# STM32-PROX_3.net
KiCad netlist of a schematic drawn in Altium Designer
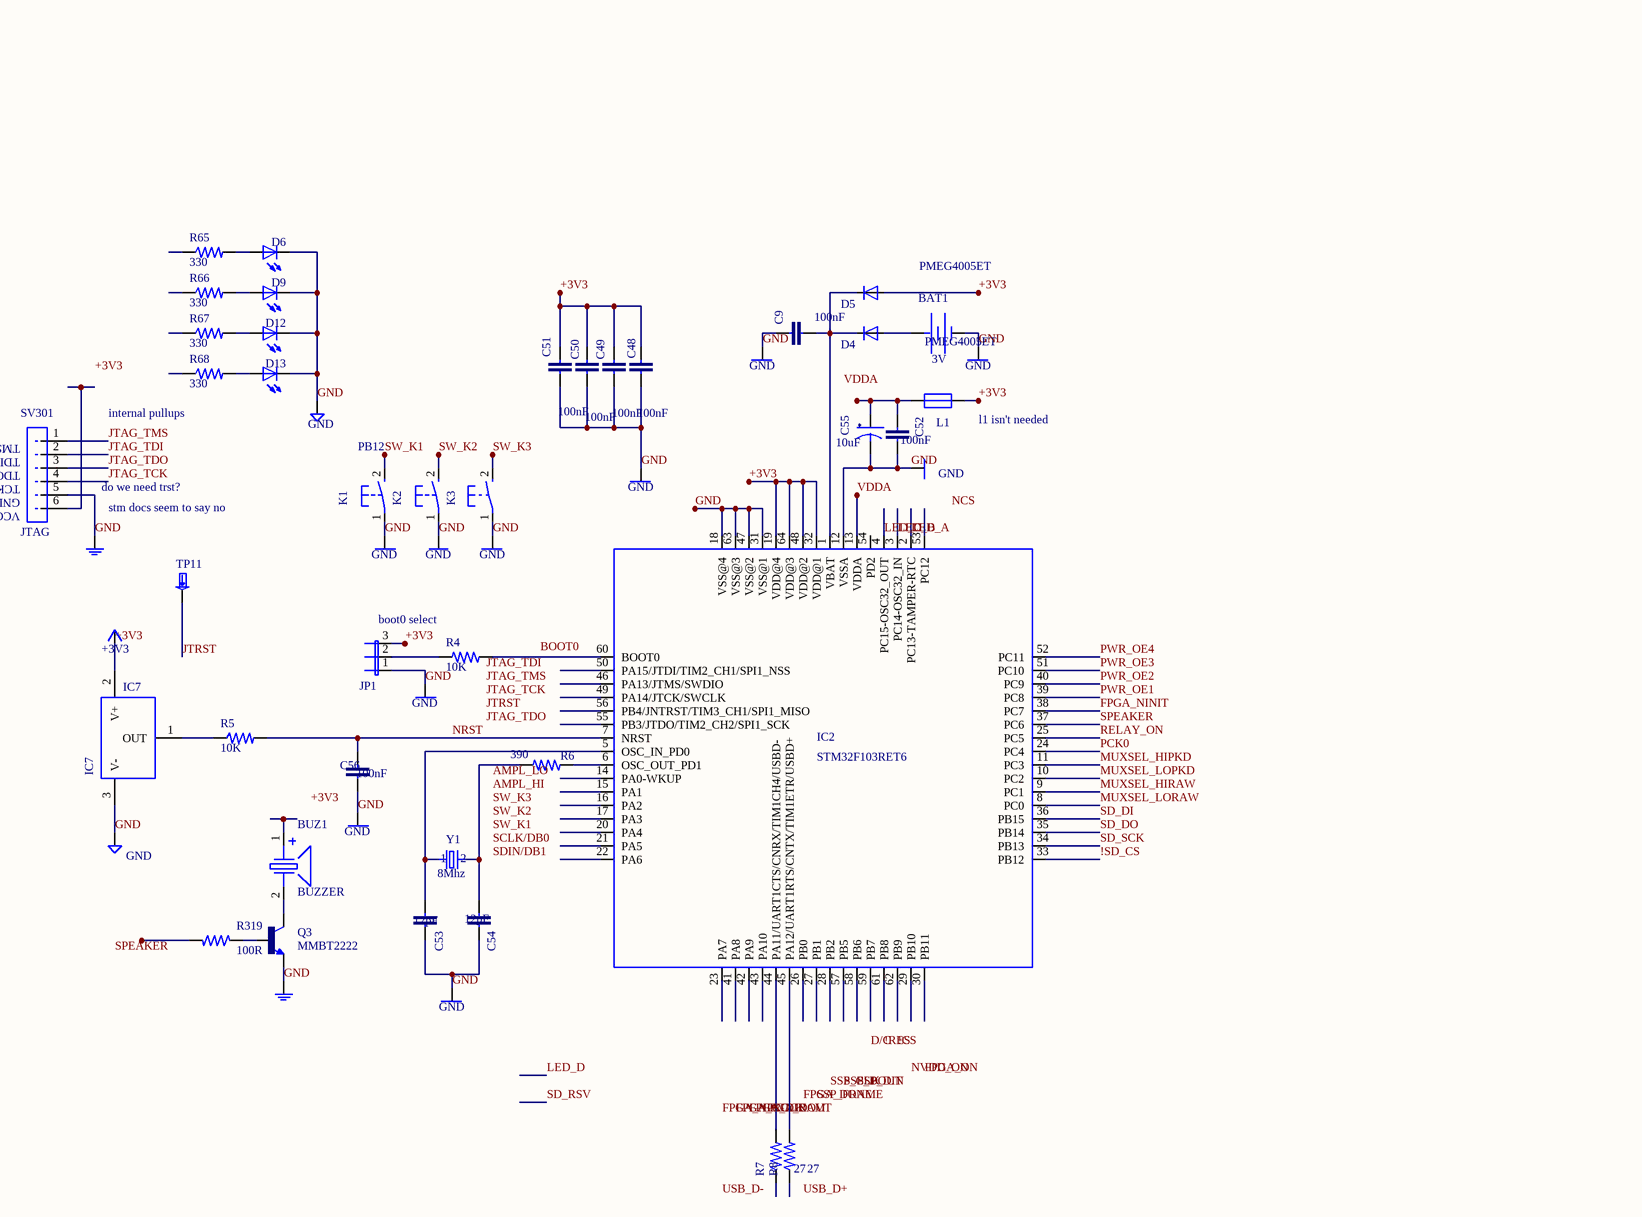
[diagram p0: STM32-PROX_3.SchDoc]

(export (version "E")
  (design (tool "Eeschema 10.0.6"))
  (components
    (comp (ref "BAT1")
      (value "3V")
      (footprint "NSL_SPARKFUN_BATTCON_12MM")
      (libsource (lib "Nullspace") (part "NSL_SPARKFUN_BATTERY12MM"))
    )
    (comp (ref "BUZ1") (value "BUZZER") (footprint "BUZZER") (libsource (lib "proxmark") (part "BUZZER")))
    (comp (ref "C9") (value "100nF") (footprint "0805") (libsource (lib "SparkFun") (part "CAP0805")))
    (comp (ref "C48") (value "100nF") (footprint "0805") (libsource (lib "SparkFun") (part "CAP0805")))
    (comp (ref "C49") (value "100nF") (footprint "0805") (libsource (lib "SparkFun") (part "CAP0805")))
    (comp (ref "C50") (value "100nF") (footprint "0805") (libsource (lib "SparkFun") (part "CAP0805")))
    (comp (ref "C51") (value "100nF") (footprint "0805") (libsource (lib "SparkFun") (part "CAP0805")))
    (comp (ref "C52") (value "100nF") (footprint "0805") (libsource (lib "SparkFun") (part "CAP0805")))
    (comp (ref "C53") (value "12pF") (footprint "0805") (libsource (lib "SparkFun") (part "CAP0805")))
    (comp (ref "C54") (value "12pF") (footprint "0805") (libsource (lib "SparkFun") (part "CAP0805")))
    (comp (ref "C55")
      (value "10uF")
      (footprint "EIA3216-KIT")
      (libsource (lib "SparkFun") (part "CAP_POL1206-KIT"))
    )
    (comp (ref "C56") (value "100nF") (footprint "0805") (libsource (lib "SparkFun") (part "CAP0805")))
    (comp (ref "D4")
      (value "PMEG4005ET")
      (footprint "SOT23-3")
      (libsource (lib "SparkFun") (part "DIODESOT23"))
    )
    (comp (ref "D5")
      (value "PMEG4005ET")
      (footprint "SOT23-3")
      (libsource (lib "SparkFun") (part "DIODESOT23"))
    )
    (comp (ref "D6") (value "~") (footprint "LED_0603") (libsource (lib "  merged") (part "LED")))
    (comp (ref "D9") (value "~") (footprint "LED_0603") (libsource (lib "  merged") (part "LED")))
    (comp (ref "D12") (value "~") (footprint "LED_0603") (libsource (lib "  merged") (part "LED")))
    (comp (ref "D13") (value "~") (footprint "LED_0603") (libsource (lib "  merged") (part "LED")))
    (comp (ref "GND1") (value "GND") (libsource (lib "") (part "GND_2")))
    (comp (ref "GND2") (value "GND") (libsource (lib "SparkFun") (part "GND")))
    (comp (ref "GND4") (value "GND") (libsource (lib "SparkFun") (part "GND")))
    (comp (ref "GND5") (value "GND") (libsource (lib "SparkFun") (part "GND")))
    (comp (ref "GND6") (value "GND") (libsource (lib "SparkFun") (part "GND")))
    (comp (ref "GND7") (value "GND") (libsource (lib "SparkFun") (part "GND")))
    (comp (ref "GND8") (value "GND") (libsource (lib "") (part "GND_2")))
    (comp (ref "GND43") (value "GND") (libsource (lib "") (part "GND_2")))
    (comp (ref "GND45") (value "GND") (libsource (lib "") (part "GND_1")))
    (comp (ref "GND46") (value "GND") (libsource (lib "SparkFun") (part "GND")))
    (comp (ref "IC2")
      (value "STM32F103RET6")
      (footprint "LQFP64_PACKAGE")
      (libsource (lib "Nullspace") (part "STM32F1_HIGH_DENSITY_LQFP64LQF64"))
    )
    (comp (ref "IC7") (value "~") (footprint "SOT23-3LEAD") (libsource (lib "  merged") (part "MCP100")))
    (comp (ref "JP1")
      (value "boot0 select")
      (footprint "JUMPER3")
      (libsource (lib "microbuilder") (part "JUMPER3"))
    )
    (comp (ref "K1") (value "~") (footprint "B3F-5XX") (libsource (lib "") (part "5-XX_1")))
    (comp (ref "K2") (value "~") (footprint "B3F-5XX") (libsource (lib "") (part "5-XX_1")))
    (comp (ref "K3") (value "~") (footprint "B3F-5XX") (libsource (lib "switch-omron") (part "5-XX")))
    (comp (ref "L1") (value "~") (footprint "0603") (libsource (lib "microbuilder") (part "FERRITE")))
    (comp (ref "Q3")
      (value "MMBT2222")
      (footprint "SOT-23-3")
      (libsource (lib "proxmark") (part "TRANSISTOR_NPNSOT23"))
    )
    (comp (ref "R4") (value "10K") (footprint "R0805") (libsource (lib "") (part "R-US_R0805_1")))
    (comp (ref "R5") (value "10K") (footprint "R0805") (libsource (lib "resistor") (part "R-US_R0805")))
    (comp (ref "R6") (value "390") (footprint "R0805") (libsource (lib "") (part "R-US_R0805_1")))
    (comp (ref "R7") (value "27") (footprint "R0805") (libsource (lib "resistor") (part "R-US_R0805")))
    (comp (ref "R8") (value "27") (footprint "R0805") (libsource (lib "resistor") (part "R-US_R0805")))
    (comp (ref "R65") (value "330") (footprint "RLC_0603") (libsource (lib "  merged") (part "RESISTOR0603")))
    (comp (ref "R66") (value "330") (footprint "RLC_0603") (libsource (lib "  merged") (part "RESISTOR0603")))
    (comp (ref "R67") (value "330") (footprint "RLC_0603") (libsource (lib "  merged") (part "RESISTOR0603")))
    (comp (ref "R68") (value "330") (footprint "RLC_0603") (libsource (lib "  merged") (part "RESISTOR0603")))
    (comp (ref "R319") (value "100R") (footprint "0603") (libsource (lib "proxmark") (part "R-US")))
    (comp (ref "SV301") (value "~") (footprint "HEADER-1X6") (libsource (lib "proxmark") (part "HEADER-1X6")))
    (comp (ref "TP11")
      (value "~")
      (footprint "KEYSTONE-PTH-TESTPOINT-5011")
      (libsource (lib "  merged") (part "TESTPADKEYSTONE-PTH"))
    )
    (comp (ref "U$10") (value "+3V3") (libsource (lib "supply1") (part "+3V3")))
    (comp (ref "V3") (value "~") (libsource (lib "proxmark") (part "AGND")))
    (comp (ref "V5") (value "~") (libsource (lib "") (part "AGND_1")))
    (comp (ref "V12") (value "GND") (libsource (lib "supply2") (part "GND")))
    (comp (ref "V40") (value "GND") (libsource (lib "supply2") (part "GND")))
    (comp (ref "Y1")
      (value "8Mhz")
      (footprint "CRYSTAL-TXC-7A")
      (libsource (lib "SparkFun-FreqCtrl") (part "CRYSTALTXC-7A"))
    )
  )
  (nets
    (net (code "3") (name "/!SD_CS") (class "Default")
      (node (ref "IC2") (pin "33") (pinfunction "PB12_33") (pintype "passive"))
    )
    (net (code "4") (name "/+3V3") (class "Default")
      (node (ref "C48") (pin "1") (pinfunction "1_1") (pintype "passive"))
      (node (ref "C49") (pin "1") (pinfunction "1_1") (pintype "passive"))
      (node (ref "C50") (pin "1") (pinfunction "1_1") (pintype "passive"))
      (node (ref "C51") (pin "1") (pinfunction "1_1") (pintype "passive"))
      (node (ref "D5") (pin "1") (pinfunction "A_1") (pintype "passive"))
      (node (ref "IC2") (pin "19") (pinfunction "VDD@4_19") (pintype "passive"))
      (node (ref "IC2") (pin "32") (pinfunction "VDD@1_32") (pintype "passive"))
      (node (ref "IC2") (pin "48") (pinfunction "VDD@2_48") (pintype "passive"))
      (node (ref "IC2") (pin "64") (pinfunction "VDD@3_64") (pintype "passive"))
      (node (ref "IC7") (pin "2") (pinfunction "V+_2") (pintype "passive"))
      (node (ref "JP1") (pin "3") (pinfunction "3_3") (pintype "passive"))
      (node (ref "L1") (pin "1") (pinfunction "P$1_1") (pintype "passive"))
      (node (ref "U$10") (pin "0") (pinfunction "+3V3_0") (pintype "passive"))
    )
    (net (code "13") (name "/FPGA_NINIT") (class "Default")
      (node (ref "IC2") (pin "38") (pinfunction "PC7_38") (pintype "passive"))
    )
    (net (code "16") (name "/GND") (class "Default")
      (node (ref "BAT1") (pin "GND") (pinfunction "-_GND") (pintype "passive"))
      (node (ref "C48") (pin "2") (pinfunction "2_2") (pintype "passive"))
      (node (ref "C49") (pin "2") (pinfunction "2_2") (pintype "passive"))
      (node (ref "C50") (pin "2") (pinfunction "2_2") (pintype "passive"))
      (node (ref "C51") (pin "2") (pinfunction "2_2") (pintype "passive"))
      (node (ref "C52") (pin "2") (pinfunction "2_2") (pintype "passive"))
      (node (ref "C53") (pin "1") (pinfunction "1_1") (pintype "passive"))
      (node (ref "C54") (pin "1") (pinfunction "1_1") (pintype "passive"))
      (node (ref "C55") (pin "C") (pinfunction "-_C") (pintype "passive"))
      (node (ref "C56") (pin "2") (pinfunction "2_2") (pintype "passive"))
      (node (ref "C9") (pin "1") (pinfunction "1_1") (pintype "passive"))
      (node (ref "D12") (pin "-") (pinfunction "C_-") (pintype "passive"))
      (node (ref "D13") (pin "-") (pinfunction "C_-") (pintype "passive"))
      (node (ref "D6") (pin "-") (pinfunction "C_-") (pintype "passive"))
      (node (ref "D9") (pin "-") (pinfunction "C_-") (pintype "passive"))
      (node (ref "GND1") (pin "0") (pinfunction "GND_0") (pintype "passive"))
      (node (ref "GND2") (pin "0") (pinfunction "GND_0") (pintype "passive"))
      (node (ref "GND4") (pin "0") (pinfunction "GND_0") (pintype "passive"))
      (node (ref "GND43") (pin "0") (pinfunction "GND_0") (pintype "passive"))
      (node (ref "GND45") (pin "0") (pinfunction "GND_0") (pintype "passive"))
      (node (ref "GND46") (pin "0") (pinfunction "GND_0") (pintype "passive"))
      (node (ref "GND5") (pin "0") (pinfunction "GND_0") (pintype "passive"))
      (node (ref "GND6") (pin "0") (pinfunction "GND_0") (pintype "passive"))
      (node (ref "GND7") (pin "0") (pinfunction "GND_0") (pintype "passive"))
      (node (ref "GND8") (pin "0") (pinfunction "GND_0") (pintype "passive"))
      (node (ref "IC2") (pin "12") (pinfunction "VSSA_12") (pintype "passive"))
      (node (ref "IC2") (pin "18") (pinfunction "VSS@4_18") (pintype "passive"))
      (node (ref "IC2") (pin "31") (pinfunction "VSS@1_31") (pintype "passive"))
      (node (ref "IC2") (pin "47") (pinfunction "VSS@2_47") (pintype "passive"))
      (node (ref "IC2") (pin "63") (pinfunction "VSS@3_63") (pintype "passive"))
      (node (ref "IC7") (pin "3") (pinfunction "V-_3") (pintype "passive"))
      (node (ref "JP1") (pin "1") (pinfunction "1_1") (pintype "passive"))
      (node (ref "K1") (pin "1") (pinfunction "P_1") (pintype "passive"))
      (node (ref "K2") (pin "1") (pinfunction "P_1") (pintype "passive"))
      (node (ref "K3") (pin "1") (pinfunction "P_1") (pintype "passive"))
      (node (ref "Q3") (pin "2") (pinfunction "E_2") (pintype "passive"))
      (node (ref "SV301") (pin "5") (pinfunction "5_5") (pintype "passive"))
      (node (ref "V12") (pin "0") (pinfunction "GND_0") (pintype "passive"))
      (node (ref "V3") (pin "0") (pinfunction "GND_0") (pintype "passive"))
      (node (ref "V40") (pin "0") (pinfunction "GND_0") (pintype "passive"))
      (node (ref "V5") (pin "0") (pinfunction "GND_0") (pintype "passive"))
    )
    (net (code "17") (name "/JTAG_TCK") (class "Default")
      (node (ref "SV301") (pin "4") (pinfunction "4_4") (pintype "passive"))
    )
    (net (code "18") (name "/JTAG_TDI") (class "Default")
      (node (ref "SV301") (pin "2") (pinfunction "2_2") (pintype "passive"))
    )
    (net (code "19") (name "/JTAG_TDO") (class "Default")
      (node (ref "SV301") (pin "3") (pinfunction "3_3") (pintype "passive"))
    )
    (net (code "20") (name "/JTAG_TMS") (class "Default")
      (node (ref "SV301") (pin "1") (pinfunction "1_1") (pintype "passive"))
    )
    (net (code "21") (name "/JTRST") (class "Default")
      (node (ref "TP11") (pin "A") (pinfunction "P$1_A") (pintype "passive"))
    )
    (net (code "22") (name "/LED_A") (class "Default")
      (node (ref "IC2") (pin "2") (pinfunction "PC13-TAMPER-RTC_2") (pintype "passive"))
    )
    (net (code "23") (name "/LED_B") (class "Default")
      (node (ref "IC2") (pin "3") (pinfunction "PC14-OSC32_IN_3") (pintype "passive"))
    )
    (net (code "24") (name "/LED_C") (class "Default")
      (node (ref "IC2") (pin "4") (pinfunction "PC15-OSC32_OUT_4") (pintype "passive"))
    )
    (net (code "26") (name "/MUXSEL_HIPKD") (class "Default")
      (node (ref "IC2") (pin "11") (pinfunction "PC3_11") (pintype "passive"))
    )
    (net (code "27") (name "/MUXSEL_HIRAW") (class "Default")
      (node (ref "IC2") (pin "9") (pinfunction "PC1_9") (pintype "passive"))
    )
    (net (code "28") (name "/MUXSEL_LOPKD") (class "Default")
      (node (ref "IC2") (pin "10") (pinfunction "PC2_10") (pintype "passive"))
    )
    (net (code "29") (name "/MUXSEL_LORAW") (class "Default")
      (node (ref "IC2") (pin "8") (pinfunction "PC0_8") (pintype "passive"))
    )
    (net (code "31") (name "/NRST") (class "Default")
      (node (ref "C56") (pin "1") (pinfunction "1_1") (pintype "passive"))
      (node (ref "IC2") (pin "7") (pinfunction "NRST_7") (pintype "passive"))
      (node (ref "R5") (pin "2") (pinfunction "2_2") (pintype "passive"))
    )
    (net (code "33") (name "/PCK0") (class "Default")
      (node (ref "IC2") (pin "24") (pinfunction "PC4_24") (pintype "passive"))
    )
    (net (code "34") (name "/PWR_OE1") (class "Default")
      (node (ref "IC2") (pin "39") (pinfunction "PC8_39") (pintype "passive"))
    )
    (net (code "35") (name "/PWR_OE2") (class "Default")
      (node (ref "IC2") (pin "40") (pinfunction "PC9_40") (pintype "passive"))
    )
    (net (code "36") (name "/PWR_OE3") (class "Default")
      (node (ref "IC2") (pin "51") (pinfunction "PC10_51") (pintype "passive"))
    )
    (net (code "37") (name "/PWR_OE4") (class "Default")
      (node (ref "IC2") (pin "52") (pinfunction "PC11_52") (pintype "passive"))
    )
    (net (code "38") (name "/RELAY_ON") (class "Default")
      (node (ref "IC2") (pin "25") (pinfunction "PC5_25") (pintype "passive"))
    )
    (net (code "41") (name "/SD_DI") (class "Default")
      (node (ref "IC2") (pin "36") (pinfunction "PB15_36") (pintype "passive"))
    )
    (net (code "42") (name "/SD_DO") (class "Default")
      (node (ref "IC2") (pin "35") (pinfunction "PB14_35") (pintype "passive"))
    )
    (net (code "44") (name "/SD_SCK") (class "Default")
      (node (ref "IC2") (pin "34") (pinfunction "PB13_34") (pintype "passive"))
    )
    (net (code "45") (name "/SPEAKER") (class "Default")
      (node (ref "IC2") (pin "37") (pinfunction "PC6_37") (pintype "passive"))
    )
    (net (code "50") (name "/SW_K1") (class "Default")
      (node (ref "K1") (pin "2") (pinfunction "S_2") (pintype "passive"))
    )
    (net (code "51") (name "/SW_K2") (class "Default")
      (node (ref "K2") (pin "2") (pinfunction "S_2") (pintype "passive"))
    )
    (net (code "52") (name "/SW_K3") (class "Default")
      (node (ref "K3") (pin "2") (pinfunction "S_2") (pintype "passive"))
    )
    (net (code "55") (name "/VDDA") (class "Default")
      (node (ref "IC2") (pin "13") (pinfunction "VDDA_13") (pintype "passive"))
    )
    (net (code "56") (name "Net-(BAT1-+)") (class "Default")
      (node (ref "BAT1") (pin "PWR@1") (pinfunction "+_PWR@1") (pintype "passive"))
      (node (ref "D4") (pin "1") (pinfunction "A_1") (pintype "passive"))
    )
    (net (code "57") (name "Net-(C55-+)") (class "Default")
      (node (ref "C52") (pin "1") (pinfunction "1_1") (pintype "passive"))
      (node (ref "C55") (pin "A") (pinfunction "+_A") (pintype "passive"))
      (node (ref "L1") (pin "2") (pinfunction "P$2_2") (pintype "passive"))
    )
    (net (code "58") (name "Net-(D4-C)") (class "Default")
      (node (ref "C9") (pin "2") (pinfunction "2_2") (pintype "passive"))
      (node (ref "D4") (pin "3") (pinfunction "C_3") (pintype "passive"))
      (node (ref "D5") (pin "3") (pinfunction "C_3") (pintype "passive"))
      (node (ref "IC2") (pin "1") (pinfunction "VBAT_1") (pintype "passive"))
    )
    (net (code "59") (name "Net-(D6-A)") (class "Default")
      (node (ref "D6") (pin "+") (pinfunction "A_+") (pintype "passive"))
      (node (ref "R65") (pin "2") (pinfunction "2_2") (pintype "passive"))
    )
    (net (code "60") (name "Net-(D9-A)") (class "Default")
      (node (ref "D9") (pin "+") (pinfunction "A_+") (pintype "passive"))
      (node (ref "R66") (pin "2") (pinfunction "2_2") (pintype "passive"))
    )
    (net (code "61") (name "Net-(D12-A)") (class "Default")
      (node (ref "D12") (pin "+") (pinfunction "A_+") (pintype "passive"))
      (node (ref "R67") (pin "2") (pinfunction "2_2") (pintype "passive"))
    )
    (net (code "62") (name "Net-(D13-A)") (class "Default")
      (node (ref "D13") (pin "+") (pinfunction "A_+") (pintype "passive"))
      (node (ref "R68") (pin "2") (pinfunction "2_2") (pintype "passive"))
    )
    (net (code "63") (name "Net-(IC2-BOOT0)") (class "Default")
      (node (ref "IC2") (pin "60") (pinfunction "BOOT0_60") (pintype "passive"))
      (node (ref "R4") (pin "2") (pinfunction "2_2") (pintype "passive"))
    )
    (net (code "64") (name "Net-(IC2-OSC_IN_PD0)") (class "Default")
      (node (ref "C53") (pin "2") (pinfunction "2_2") (pintype "passive"))
      (node (ref "IC2") (pin "5") (pinfunction "OSC_IN_PD0_5") (pintype "passive"))
      (node (ref "Y1") (pin "P$1") (pinfunction "1_P$1") (pintype "passive"))
    )
    (net (code "65") (name "Net-(IC2-OSC_OUT_PD1)") (class "Default")
      (node (ref "IC2") (pin "6") (pinfunction "OSC_OUT_PD1_6") (pintype "passive"))
      (node (ref "R6") (pin "2") (pinfunction "2_2") (pintype "passive"))
    )
    (net (code "66") (name "Net-(IC2-PA11{slash}UART1CTS{slash}CNRX{slash}TIM1CH4{slash}USBD-)") (class "Default")
      (node (ref "IC2") (pin "44") (pinfunction "PA11/UART1CTS/CNRX/TIM1CH4/USBD-_44") (pintype "passive"))
      (node (ref "R7") (pin "2") (pinfunction "2_2") (pintype "passive"))
    )
    (net (code "67") (name "Net-(IC2-PA12{slash}UART1RTS{slash}CNTX{slash}TIM1ETR{slash}USBD+)") (class "Default")
      (node (ref "IC2") (pin "45") (pinfunction "PA12/UART1RTS/CNTX/TIM1ETR/USBD+_45") (pintype "passive"))
      (node (ref "R8") (pin "2") (pinfunction "2_2") (pintype "passive"))
    )
    (net (code "68") (name "Net-(IC7-OUT)") (class "Default")
      (node (ref "IC7") (pin "1") (pinfunction "OUT_1") (pintype "passive"))
      (node (ref "R5") (pin "1") (pinfunction "1_1") (pintype "passive"))
    )
    (net (code "69") (name "Net-(JP1-Pad2)") (class "Default")
      (node (ref "JP1") (pin "2") (pinfunction "2_2") (pintype "passive"))
      (node (ref "R4") (pin "1") (pinfunction "1_1") (pintype "passive"))
    )
    (net (code "70") (name "Net-(Q3-B)") (class "Default")
      (node (ref "Q3") (pin "1") (pinfunction "B_1") (pintype "passive"))
      (node (ref "R319") (pin "1") (pinfunction "1_1") (pintype "passive"))
    )
    (net (code "71") (name "Net-(Q3-C)") (class "Default")
      (node (ref "BUZ1") (pin "2") (pinfunction "2_2") (pintype "passive"))
      (node (ref "Q3") (pin "3") (pinfunction "C_3") (pintype "passive"))
    )
    (net (code "72") (name "Net-(Y1-2)") (class "Default")
      (node (ref "C54") (pin "2") (pinfunction "2_2") (pintype "passive"))
      (node (ref "R6") (pin "1") (pinfunction "1_1") (pintype "passive"))
      (node (ref "Y1") (pin "P$2") (pinfunction "2_P$2") (pintype "passive"))
    )
    (net (code "73") (name "unconnected-(BUZ1-Pad1)") (class "Default")
      (node (ref "BUZ1") (pin "1") (pinfunction "1_1") (pintype "passive"))
    )
    (net (code "74") (name "unconnected-(IC2-PA0-WKUP-Pad14)") (class "Default")
      (node (ref "IC2") (pin "14") (pinfunction "PA0-WKUP_14") (pintype "passive"))
    )
    (net (code "75") (name "unconnected-(IC2-PA1-Pad15)") (class "Default")
      (node (ref "IC2") (pin "15") (pinfunction "PA1_15") (pintype "passive"))
    )
    (net (code "76") (name "unconnected-(IC2-PA2-Pad16)") (class "Default")
      (node (ref "IC2") (pin "16") (pinfunction "PA2_16") (pintype "passive"))
    )
    (net (code "77") (name "unconnected-(IC2-PA3-Pad17)") (class "Default")
      (node (ref "IC2") (pin "17") (pinfunction "PA3_17") (pintype "passive"))
    )
    (net (code "78") (name "unconnected-(IC2-PA4-Pad20)") (class "Default")
      (node (ref "IC2") (pin "20") (pinfunction "PA4_20") (pintype "passive"))
    )
    (net (code "79") (name "unconnected-(IC2-PA5-Pad21)") (class "Default")
      (node (ref "IC2") (pin "21") (pinfunction "PA5_21") (pintype "passive"))
    )
    (net (code "80") (name "unconnected-(IC2-PA6-Pad22)") (class "Default")
      (node (ref "IC2") (pin "22") (pinfunction "PA6_22") (pintype "passive"))
    )
    (net (code "81") (name "unconnected-(IC2-PA7-Pad23)") (class "Default")
      (node (ref "IC2") (pin "23") (pinfunction "PA7_23") (pintype "passive"))
    )
    (net (code "82") (name "unconnected-(IC2-PA8-Pad41)") (class "Default")
      (node (ref "IC2") (pin "41") (pinfunction "PA8_41") (pintype "passive"))
    )
    (net (code "83") (name "unconnected-(IC2-PA9-Pad42)") (class "Default")
      (node (ref "IC2") (pin "42") (pinfunction "PA9_42") (pintype "passive"))
    )
    (net (code "84") (name "unconnected-(IC2-PA10-Pad43)") (class "Default")
      (node (ref "IC2") (pin "43") (pinfunction "PA10_43") (pintype "passive"))
    )
    (net (code "85") (name "unconnected-(IC2-PA13{slash}JTMS{slash}SWDIO-Pad46)") (class "Default")
      (node (ref "IC2") (pin "46") (pinfunction "PA13/JTMS/SWDIO_46") (pintype "passive"))
    )
    (net (code "86") (name "unconnected-(IC2-PA14{slash}JTCK{slash}SWCLK-Pad49)") (class "Default")
      (node (ref "IC2") (pin "49") (pinfunction "PA14/JTCK/SWCLK_49") (pintype "passive"))
    )
    (net (code "87") (name "unconnected-(IC2-PA15{slash}JTDI{slash}TIM2_CH1{slash}SPI1_NSS-Pad50)") (class "Default")
      (node (ref "IC2") (pin "50") (pinfunction "PA15/JTDI/TIM2_CH1/SPI1_NSS_50") (pintype "passive"))
    )
    (net (code "88") (name "unconnected-(IC2-PB0-Pad26)") (class "Default")
      (node (ref "IC2") (pin "26") (pinfunction "PB0_26") (pintype "passive"))
    )
    (net (code "89") (name "unconnected-(IC2-PB1-Pad27)") (class "Default")
      (node (ref "IC2") (pin "27") (pinfunction "PB1_27") (pintype "passive"))
    )
    (net (code "90") (name "unconnected-(IC2-PB2-Pad28)") (class "Default")
      (node (ref "IC2") (pin "28") (pinfunction "PB2_28") (pintype "passive"))
    )
    (net (code "91") (name "unconnected-(IC2-PB3{slash}JTDO{slash}TIM2_CH2{slash}SPI1_SCK-Pad55)") (class "Default")
      (node (ref "IC2") (pin "55") (pinfunction "PB3/JTDO/TIM2_CH2/SPI1_SCK_55") (pintype "passive"))
    )
    (net (code "92") (name "unconnected-(IC2-PB4{slash}JNTRST{slash}TIM3_CH1{slash}SPI1_MISO-Pad56)") (class "Default")
      (node (ref "IC2") (pin "56") (pinfunction "PB4/JNTRST/TIM3_CH1/SPI1_MISO_56") (pintype "passive"))
    )
    (net (code "93") (name "unconnected-(IC2-PB5-Pad57)") (class "Default")
      (node (ref "IC2") (pin "57") (pinfunction "PB5_57") (pintype "passive"))
    )
    (net (code "94") (name "unconnected-(IC2-PB6-Pad58)") (class "Default")
      (node (ref "IC2") (pin "58") (pinfunction "PB6_58") (pintype "passive"))
    )
    (net (code "95") (name "unconnected-(IC2-PB7-Pad59)") (class "Default")
      (node (ref "IC2") (pin "59") (pinfunction "PB7_59") (pintype "passive"))
    )
    (net (code "96") (name "unconnected-(IC2-PB8-Pad61)") (class "Default")
      (node (ref "IC2") (pin "61") (pinfunction "PB8_61") (pintype "passive"))
    )
    (net (code "97") (name "unconnected-(IC2-PB9-Pad62)") (class "Default")
      (node (ref "IC2") (pin "62") (pinfunction "PB9_62") (pintype "passive"))
    )
    (net (code "98") (name "unconnected-(IC2-PB10-Pad29)") (class "Default")
      (node (ref "IC2") (pin "29") (pinfunction "PB10_29") (pintype "passive"))
    )
    (net (code "99") (name "unconnected-(IC2-PB11-Pad30)") (class "Default")
      (node (ref "IC2") (pin "30") (pinfunction "PB11_30") (pintype "passive"))
    )
    (net (code "100") (name "unconnected-(IC2-PC12-Pad53)") (class "Default")
      (node (ref "IC2") (pin "53") (pinfunction "PC12_53") (pintype "passive"))
    )
    (net (code "101") (name "unconnected-(IC2-PD2-Pad54)") (class "Default")
      (node (ref "IC2") (pin "54") (pinfunction "PD2_54") (pintype "passive"))
    )
    (net (code "102") (name "unconnected-(R7-Pad1)") (class "Default")
      (node (ref "R7") (pin "1") (pinfunction "1_1") (pintype "passive"))
    )
    (net (code "103") (name "unconnected-(R8-Pad1)") (class "Default")
      (node (ref "R8") (pin "1") (pinfunction "1_1") (pintype "passive"))
    )
    (net (code "104") (name "unconnected-(R65-Pad1)") (class "Default")
      (node (ref "R65") (pin "1") (pinfunction "1_1") (pintype "passive"))
    )
    (net (code "105") (name "unconnected-(R66-Pad1)") (class "Default")
      (node (ref "R66") (pin "1") (pinfunction "1_1") (pintype "passive"))
    )
    (net (code "106") (name "unconnected-(R67-Pad1)") (class "Default")
      (node (ref "R67") (pin "1") (pinfunction "1_1") (pintype "passive"))
    )
    (net (code "107") (name "unconnected-(R68-Pad1)") (class "Default")
      (node (ref "R68") (pin "1") (pinfunction "1_1") (pintype "passive"))
    )
    (net (code "108") (name "unconnected-(R319-Pad2)") (class "Default")
      (node (ref "R319") (pin "2") (pinfunction "2_2") (pintype "passive"))
    )
    (net (code "109") (name "unconnected-(SV301-Pad6)") (class "Default")
      (node (ref "SV301") (pin "6") (pinfunction "6_6") (pintype "passive"))
    )
  )
)
